# voicemodulator_schm.net
KiCad netlist of a schematic drawn in EAGLE
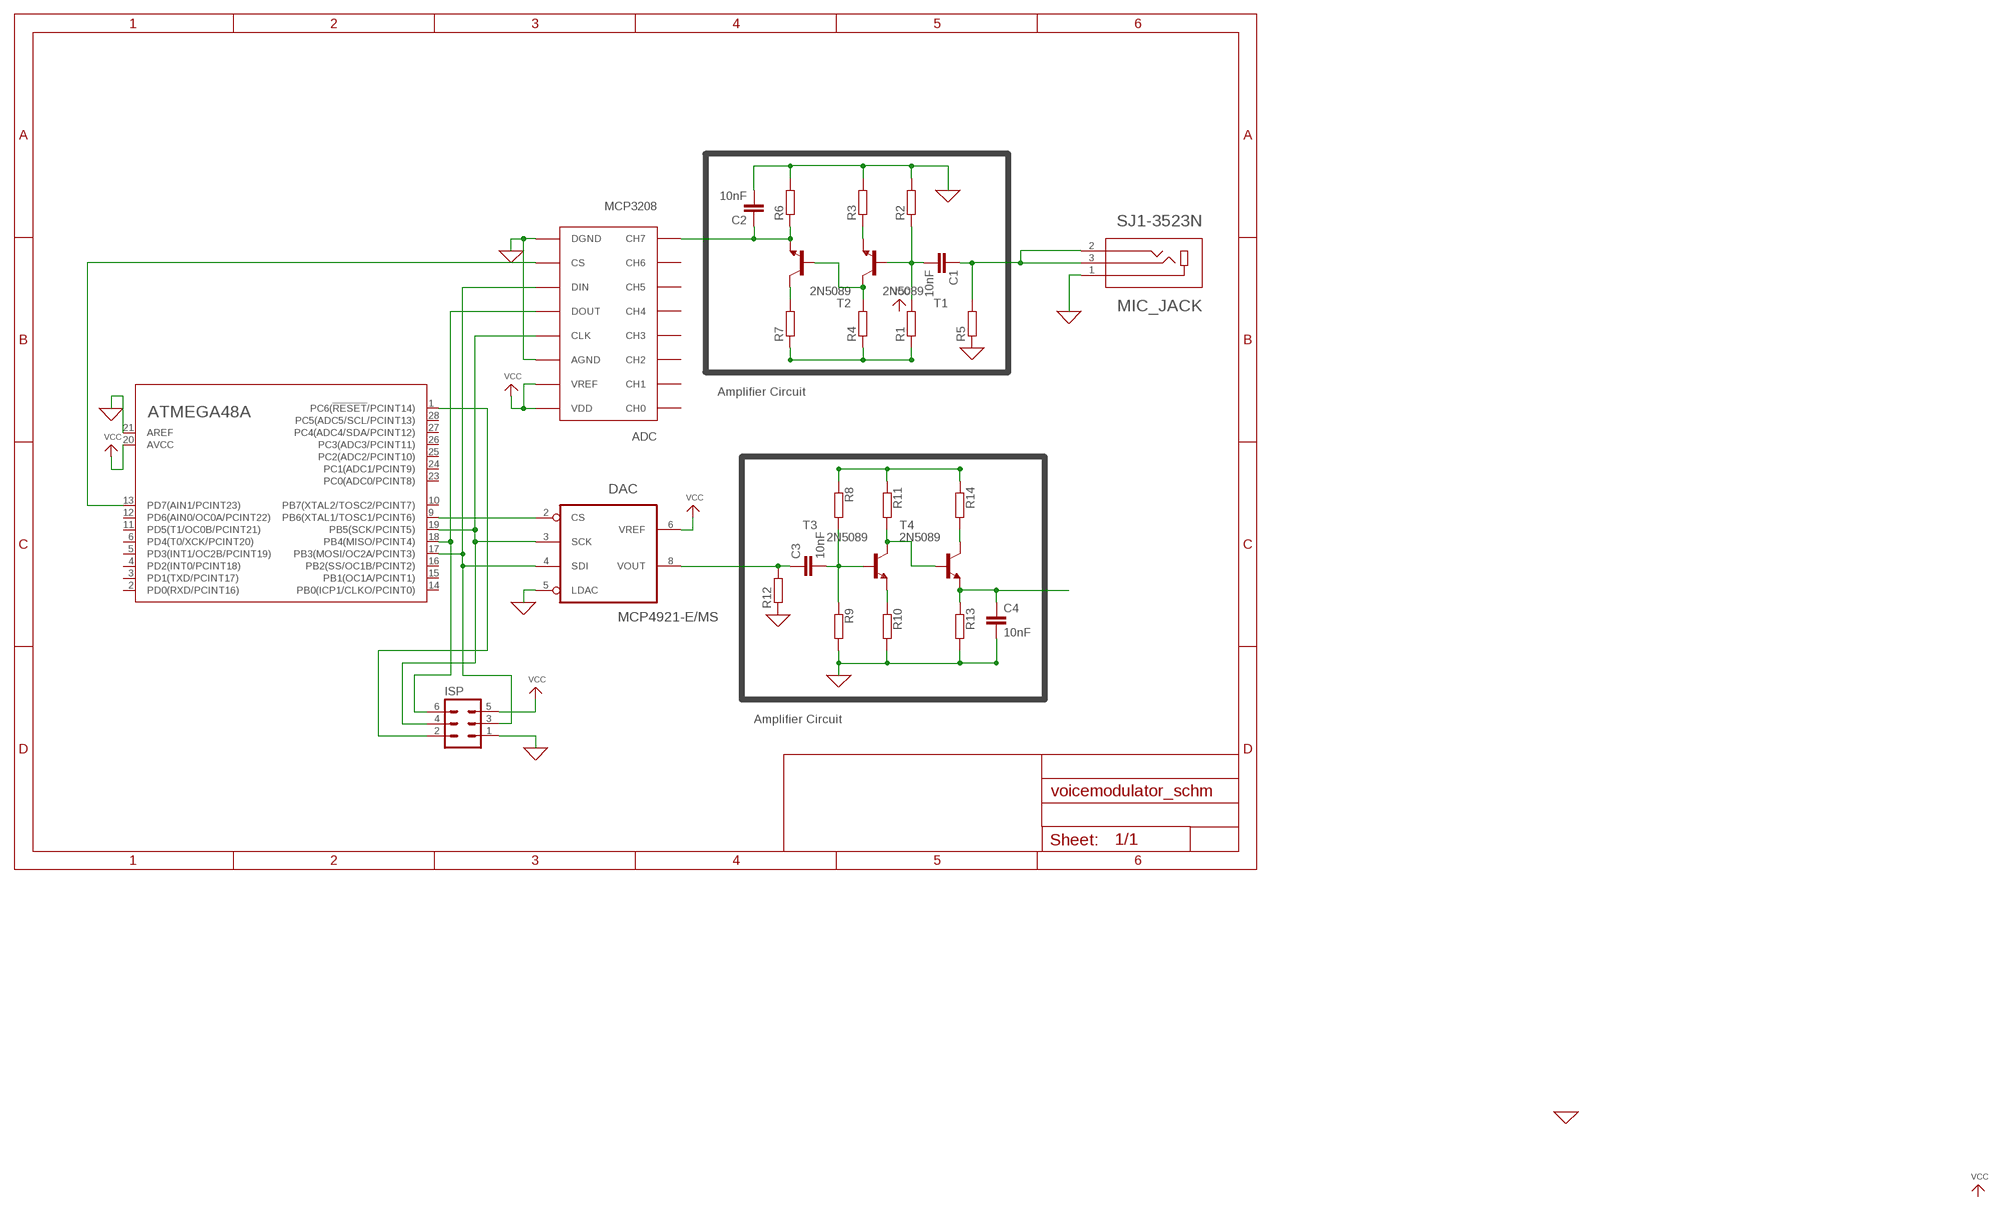
[diagram p0: schematic, sheet 1]

(export (version "E")
  (design (tool "Eeschema 10.0.6"))
  (components
    (comp (ref "ADC")
      (value "MCP3208")
      (footprint "eagle-import:DIL16")
      (libsource (lib "eagle-import") (part "MCP3208"))
    )
    (comp (ref "ATMEGA48A")
      (value "ATMEGA48/88/168/328-PU(DIP28)PU")
      (footprint "eagle-import:DIL28")
      (libsource (lib "eagle-import") (part "ATMEGA48/88/168/328-PU(DIP28)PU"))
    )
    (comp (ref "C1")
      (value "10nF")
      (footprint "eagle-import:0603")
      (libsource (lib "eagle-import") (part "10NF-0603-50V-10%"))
    )
    (comp (ref "C2")
      (value "10nF")
      (footprint "eagle-import:0603")
      (libsource (lib "eagle-import") (part "10NF-0603-50V-10%"))
    )
    (comp (ref "C3")
      (value "10nF")
      (footprint "eagle-import:0603")
      (libsource (lib "eagle-import") (part "10NF-0603-50V-10%"))
    )
    (comp (ref "C4")
      (value "10nF")
      (footprint "eagle-import:0603")
      (libsource (lib "eagle-import") (part "10NF-0603-50V-10%"))
    )
    (comp (ref "DAC")
      (value "MCP4921-E/MS")
      (footprint "eagle-import:MSOP-8")
      (libsource (lib "eagle-import") (part "MCP491-E/MS2"))
    )
    (comp (ref "ISP")
      (value "MA03-2")
      (footprint "eagle-import:MA03-2")
      (libsource (lib "eagle-import") (part "MA03-2"))
    )
    (comp (ref "MIC_JACK")
      (value "SJ1-3523N")
      (footprint "eagle-import:CUI_SJ1-3523N")
      (fields (field (name "MANUFACTURER") "CUI"))
      (libsource (lib "eagle-import") (part "SJ1-3523N"))
    )
    (comp (ref "R1")
      (value "SMR-WAV")
      (footprint "eagle-import:SMS-WAV")
      (libsource (lib "eagle-import") (part "SMR-WAV"))
    )
    (comp (ref "R2")
      (value "SMR-WAV")
      (footprint "eagle-import:SMS-WAV")
      (libsource (lib "eagle-import") (part "SMR-WAV"))
    )
    (comp (ref "R3")
      (value "SMR-WAV")
      (footprint "eagle-import:SMS-WAV")
      (libsource (lib "eagle-import") (part "SMR-WAV"))
    )
    (comp (ref "R4")
      (value "SMR-WAV")
      (footprint "eagle-import:SMS-WAV")
      (libsource (lib "eagle-import") (part "SMR-WAV"))
    )
    (comp (ref "R5")
      (value "SMR-WAV")
      (footprint "eagle-import:SMS-WAV")
      (libsource (lib "eagle-import") (part "SMR-WAV"))
    )
    (comp (ref "R6")
      (value "SMR-WAV")
      (footprint "eagle-import:SMS-WAV")
      (libsource (lib "eagle-import") (part "SMR-WAV"))
    )
    (comp (ref "R7")
      (value "SMR-WAV")
      (footprint "eagle-import:SMS-WAV")
      (libsource (lib "eagle-import") (part "SMR-WAV"))
    )
    (comp (ref "R8")
      (value "SMR-WAV")
      (footprint "eagle-import:SMS-WAV")
      (libsource (lib "eagle-import") (part "SMR-WAV"))
    )
    (comp (ref "R9")
      (value "SMR-WAV")
      (footprint "eagle-import:SMS-WAV")
      (libsource (lib "eagle-import") (part "SMR-WAV"))
    )
    (comp (ref "R10")
      (value "SMR-WAV")
      (footprint "eagle-import:SMS-WAV")
      (libsource (lib "eagle-import") (part "SMR-WAV"))
    )
    (comp (ref "R11")
      (value "SMR-WAV")
      (footprint "eagle-import:SMS-WAV")
      (libsource (lib "eagle-import") (part "SMR-WAV"))
    )
    (comp (ref "R12")
      (value "SMR-WAV")
      (footprint "eagle-import:SMS-WAV")
      (libsource (lib "eagle-import") (part "SMR-WAV"))
    )
    (comp (ref "R13")
      (value "SMR-WAV")
      (footprint "eagle-import:SMS-WAV")
      (libsource (lib "eagle-import") (part "SMR-WAV"))
    )
    (comp (ref "R14")
      (value "SMR-WAV")
      (footprint "eagle-import:SMS-WAV")
      (libsource (lib "eagle-import") (part "SMR-WAV"))
    )
    (comp (ref "T1")
      (value "2N5089")
      (footprint "eagle-import:TO92")
      (libsource (lib "eagle-import") (part "2N5089"))
    )
    (comp (ref "T2")
      (value "2N5089")
      (footprint "eagle-import:TO92")
      (libsource (lib "eagle-import") (part "2N5089"))
    )
    (comp (ref "T3")
      (value "2N5089")
      (footprint "eagle-import:TO92")
      (libsource (lib "eagle-import") (part "2N5089"))
    )
    (comp (ref "T4")
      (value "2N5089")
      (footprint "eagle-import:TO92")
      (libsource (lib "eagle-import") (part "2N5089"))
    )
  )
  (nets
    (net (code "1") (name "GND") (class "Default")
      (node (ref "ADC") (pin "AGND") (pinfunction "AGND_AGND") (pintype "power_in"))
      (node (ref "ADC") (pin "DGND") (pinfunction "DGND_DGND") (pintype "power_in"))
      (node (ref "ATMEGA48A") (pin "21") (pinfunction "AREF_21") (pintype "passive"))
      (node (ref "C2") (pin "2") (pinfunction "2_2") (pintype "passive"))
      (node (ref "C4") (pin "2") (pinfunction "2_2") (pintype "passive"))
      (node (ref "DAC") (pin "5") (pinfunction "LDAC_5") (pintype "input"))
      (node (ref "ISP") (pin "1") (pinfunction "1_1") (pintype "passive"))
      (node (ref "MIC_JACK") (pin "1") (pinfunction "1_1") (pintype "passive"))
      (node (ref "R10") (pin "1") (pinfunction "1_1") (pintype "passive"))
      (node (ref "R12") (pin "2") (pinfunction "2_2") (pintype "passive"))
      (node (ref "R13") (pin "1") (pinfunction "1_1") (pintype "passive"))
      (node (ref "R2") (pin "1") (pinfunction "1_1") (pintype "passive"))
      (node (ref "R3") (pin "1") (pinfunction "1_1") (pintype "passive"))
      (node (ref "R5") (pin "2") (pinfunction "2_2") (pintype "passive"))
      (node (ref "R6") (pin "1") (pinfunction "1_1") (pintype "passive"))
      (node (ref "R9") (pin "1") (pinfunction "1_1") (pintype "passive"))
    )
    (net (code "2") (name "Net-(ATMEGA48AA-PB3(MOSI{slash}OC2A{slash}PCINT3))") (class "Default")
      (node (ref "ADC") (pin "DIN") (pinfunction "DIN_DIN") (pintype "input"))
      (node (ref "ATMEGA48A") (pin "17") (pinfunction "PB3(MOSI/OC2A/PCINT3)_17") (pintype "bidirectional"))
      (node (ref "DAC") (pin "4") (pinfunction "SDI_4") (pintype "input"))
      (node (ref "ISP") (pin "3") (pinfunction "3_3") (pintype "passive"))
    )
    (net (code "3") (name "Net-(ATMEGA48AA-PB4(MISO{slash}PCINT4))") (class "Default")
      (node (ref "ADC") (pin "DOUT") (pinfunction "DOUT_DOUT") (pintype "output"))
      (node (ref "ATMEGA48A") (pin "18") (pinfunction "PB4(MISO/PCINT4)_18") (pintype "bidirectional"))
      (node (ref "ISP") (pin "6") (pinfunction "6_6") (pintype "passive"))
    )
    (net (code "4") (name "Net-(ATMEGA48AA-PB5(SCK{slash}PCINT5))") (class "Default")
      (node (ref "ADC") (pin "CLK") (pinfunction "CLK_CLK") (pintype "input"))
      (node (ref "ATMEGA48A") (pin "19") (pinfunction "PB5(SCK/PCINT5)_19") (pintype "bidirectional"))
      (node (ref "DAC") (pin "3") (pinfunction "SCK_3") (pintype "input"))
      (node (ref "ISP") (pin "4") (pinfunction "4_4") (pintype "passive"))
    )
    (net (code "5") (name "Net-(ATMEGA48AA-PB6(XTAL1{slash}TOSC1{slash}PCINT6))") (class "Default")
      (node (ref "ATMEGA48A") (pin "9") (pinfunction "PB6(XTAL1/TOSC1/PCINT6)_9") (pintype "bidirectional"))
      (node (ref "DAC") (pin "2") (pinfunction "CS_2") (pintype "input"))
    )
    (net (code "6") (name "Net-(ATMEGA48AA-PC6(~{RESET}{slash}PCINT14))") (class "Default")
      (node (ref "ATMEGA48A") (pin "1") (pinfunction "PC6(~{RESET}/PCINT14)_1") (pintype "bidirectional"))
      (node (ref "ISP") (pin "2") (pinfunction "2_2") (pintype "passive"))
    )
    (net (code "7") (name "Net-(ATMEGA48AA-PD7(AIN1{slash}PCINT23))") (class "Default")
      (node (ref "ADC") (pin "CS") (pinfunction "CS_CS") (pintype "input"))
      (node (ref "ATMEGA48A") (pin "13") (pinfunction "PD7(AIN1/PCINT23)_13") (pintype "bidirectional"))
    )
    (net (code "8") (name "Net-(C1-Pad1)") (class "Default")
      (node (ref "C1") (pin "1") (pinfunction "1_1") (pintype "passive"))
      (node (ref "MIC_JACK") (pin "2") (pinfunction "2_2") (pintype "passive"))
      (node (ref "MIC_JACK") (pin "3") (pinfunction "3_3") (pintype "passive"))
      (node (ref "R5") (pin "1") (pinfunction "1_1") (pintype "passive"))
    )
    (net (code "9") (name "Net-(DACA-VOUT)") (class "Default")
      (node (ref "C3") (pin "1") (pinfunction "1_1") (pintype "passive"))
      (node (ref "DAC") (pin "8") (pinfunction "VOUT_8") (pintype "output"))
      (node (ref "R12") (pin "1") (pinfunction "1_1") (pintype "passive"))
    )
    (net (code "10") (name "Net-(R1-Pad2)") (class "Default")
      (node (ref "R1") (pin "2") (pinfunction "2_2") (pintype "passive"))
      (node (ref "R4") (pin "2") (pinfunction "2_2") (pintype "passive"))
      (node (ref "R7") (pin "2") (pinfunction "2_2") (pintype "passive"))
    )
    (net (code "11") (name "Net-(R11-Pad2)") (class "Default")
      (node (ref "R11") (pin "2") (pinfunction "2_2") (pintype "passive"))
      (node (ref "R14") (pin "2") (pinfunction "2_2") (pintype "passive"))
      (node (ref "R8") (pin "2") (pinfunction "2_2") (pintype "passive"))
    )
    (net (code "12") (name "Net-(T1-B)") (class "Default")
      (node (ref "C1") (pin "2") (pinfunction "2_2") (pintype "passive"))
      (node (ref "R1") (pin "1") (pinfunction "1_1") (pintype "passive"))
      (node (ref "R2") (pin "2") (pinfunction "2_2") (pintype "passive"))
      (node (ref "T1") (pin "2") (pinfunction "B_2") (pintype "passive"))
    )
    (net (code "13") (name "Net-(T1-C)") (class "Default")
      (node (ref "R4") (pin "1") (pinfunction "1_1") (pintype "passive"))
      (node (ref "T1") (pin "1") (pinfunction "C_1") (pintype "passive"))
      (node (ref "T2") (pin "2") (pinfunction "B_2") (pintype "passive"))
    )
    (net (code "14") (name "Net-(T1-E)") (class "Default")
      (node (ref "R3") (pin "2") (pinfunction "2_2") (pintype "passive"))
      (node (ref "T1") (pin "3") (pinfunction "E_3") (pintype "passive"))
    )
    (net (code "15") (name "Net-(T2-C)") (class "Default")
      (node (ref "R7") (pin "1") (pinfunction "1_1") (pintype "passive"))
      (node (ref "T2") (pin "1") (pinfunction "C_1") (pintype "passive"))
    )
    (net (code "16") (name "Net-(T2-E)") (class "Default")
      (node (ref "ADC") (pin "CH7") (pinfunction "CH7_CH7") (pintype "input"))
      (node (ref "C2") (pin "1") (pinfunction "1_1") (pintype "passive"))
      (node (ref "R6") (pin "2") (pinfunction "2_2") (pintype "passive"))
      (node (ref "T2") (pin "3") (pinfunction "E_3") (pintype "passive"))
    )
    (net (code "17") (name "Net-(T3-B)") (class "Default")
      (node (ref "C3") (pin "2") (pinfunction "2_2") (pintype "passive"))
      (node (ref "R8") (pin "1") (pinfunction "1_1") (pintype "passive"))
      (node (ref "R9") (pin "2") (pinfunction "2_2") (pintype "passive"))
      (node (ref "T3") (pin "2") (pinfunction "B_2") (pintype "passive"))
    )
    (net (code "18") (name "Net-(T3-C)") (class "Default")
      (node (ref "R11") (pin "1") (pinfunction "1_1") (pintype "passive"))
      (node (ref "T3") (pin "1") (pinfunction "C_1") (pintype "passive"))
      (node (ref "T4") (pin "2") (pinfunction "B_2") (pintype "passive"))
    )
    (net (code "19") (name "Net-(T3-E)") (class "Default")
      (node (ref "R10") (pin "2") (pinfunction "2_2") (pintype "passive"))
      (node (ref "T3") (pin "3") (pinfunction "E_3") (pintype "passive"))
    )
    (net (code "20") (name "Net-(T4-C)") (class "Default")
      (node (ref "R14") (pin "1") (pinfunction "1_1") (pintype "passive"))
      (node (ref "T4") (pin "1") (pinfunction "C_1") (pintype "passive"))
    )
    (net (code "21") (name "Net-(T4-E)") (class "Default")
      (node (ref "C4") (pin "1") (pinfunction "1_1") (pintype "passive"))
      (node (ref "R13") (pin "2") (pinfunction "2_2") (pintype "passive"))
      (node (ref "T4") (pin "3") (pinfunction "E_3") (pintype "passive"))
    )
    (net (code "22") (name "VCC") (class "Default")
      (node (ref "ADC") (pin "VDD") (pinfunction "VDD_VDD") (pintype "power_in"))
      (node (ref "ADC") (pin "VREF") (pinfunction "VREF_VREF") (pintype "input"))
      (node (ref "ATMEGA48A") (pin "20") (pinfunction "AVCC_20") (pintype "power_in"))
      (node (ref "DAC") (pin "6") (pinfunction "VREF_6") (pintype "input"))
      (node (ref "ISP") (pin "5") (pinfunction "5_5") (pintype "passive"))
    )
    (net (code "23") (name "unconnected-(ADC-PadCH0)") (class "Default")
      (node (ref "ADC") (pin "CH0") (pinfunction "CH0_CH0") (pintype "input"))
    )
    (net (code "24") (name "unconnected-(ADC-PadCH1)") (class "Default")
      (node (ref "ADC") (pin "CH1") (pinfunction "CH1_CH1") (pintype "input"))
    )
    (net (code "25") (name "unconnected-(ADC-PadCH2)") (class "Default")
      (node (ref "ADC") (pin "CH2") (pinfunction "CH2_CH2") (pintype "input"))
    )
    (net (code "26") (name "unconnected-(ADC-PadCH3)") (class "Default")
      (node (ref "ADC") (pin "CH3") (pinfunction "CH3_CH3") (pintype "input"))
    )
    (net (code "27") (name "unconnected-(ADC-PadCH4)") (class "Default")
      (node (ref "ADC") (pin "CH4") (pinfunction "CH4_CH4") (pintype "input"))
    )
    (net (code "28") (name "unconnected-(ADC-PadCH5)") (class "Default")
      (node (ref "ADC") (pin "CH5") (pinfunction "CH5_CH5") (pintype "input"))
    )
    (net (code "29") (name "unconnected-(ADC-PadCH6)") (class "Default")
      (node (ref "ADC") (pin "CH6") (pinfunction "CH6_CH6") (pintype "input"))
    )
    (net (code "30") (name "unconnected-(ATMEGA48AA-PB0(ICP1{slash}CLKO{slash}PCINT0)-Pad14)") (class "Default")
      (node (ref "ATMEGA48A") (pin "14") (pinfunction "PB0(ICP1/CLKO/PCINT0)_14") (pintype "bidirectional"))
    )
    (net (code "31") (name "unconnected-(ATMEGA48AA-PB1(OC1A{slash}PCINT1)-Pad15)") (class "Default")
      (node (ref "ATMEGA48A") (pin "15") (pinfunction "PB1(OC1A/PCINT1)_15") (pintype "bidirectional"))
    )
    (net (code "32") (name "unconnected-(ATMEGA48AA-PB2(SS{slash}OC1B{slash}PCINT2)-Pad16)") (class "Default")
      (node (ref "ATMEGA48A") (pin "16") (pinfunction "PB2(SS/OC1B/PCINT2)_16") (pintype "bidirectional"))
    )
    (net (code "33") (name "unconnected-(ATMEGA48AA-PB7(XTAL2{slash}TOSC2{slash}PCINT7)-Pad10)") (class "Default")
      (node (ref "ATMEGA48A") (pin "10") (pinfunction "PB7(XTAL2/TOSC2/PCINT7)_10") (pintype "bidirectional"))
    )
    (net (code "34") (name "unconnected-(ATMEGA48AA-PC0(ADC0{slash}PCINT8)-Pad23)") (class "Default")
      (node (ref "ATMEGA48A") (pin "23") (pinfunction "PC0(ADC0/PCINT8)_23") (pintype "bidirectional"))
    )
    (net (code "35") (name "unconnected-(ATMEGA48AA-PC1(ADC1{slash}PCINT9)-Pad24)") (class "Default")
      (node (ref "ATMEGA48A") (pin "24") (pinfunction "PC1(ADC1/PCINT9)_24") (pintype "bidirectional"))
    )
    (net (code "36") (name "unconnected-(ATMEGA48AA-PC2(ADC2{slash}PCINT10)-Pad25)") (class "Default")
      (node (ref "ATMEGA48A") (pin "25") (pinfunction "PC2(ADC2/PCINT10)_25") (pintype "bidirectional"))
    )
    (net (code "37") (name "unconnected-(ATMEGA48AA-PC3(ADC3{slash}PCINT11)-Pad26)") (class "Default")
      (node (ref "ATMEGA48A") (pin "26") (pinfunction "PC3(ADC3/PCINT11)_26") (pintype "bidirectional"))
    )
    (net (code "38") (name "unconnected-(ATMEGA48AA-PC4(ADC4{slash}SDA{slash}PCINT12)-Pad27)") (class "Default")
      (node (ref "ATMEGA48A") (pin "27") (pinfunction "PC4(ADC4/SDA/PCINT12)_27") (pintype "bidirectional"))
    )
    (net (code "39") (name "unconnected-(ATMEGA48AA-PC5(ADC5{slash}SCL{slash}PCINT13)-Pad28)") (class "Default")
      (node (ref "ATMEGA48A") (pin "28") (pinfunction "PC5(ADC5/SCL/PCINT13)_28") (pintype "bidirectional"))
    )
    (net (code "40") (name "unconnected-(ATMEGA48AA-PD0(RXD{slash}PCINT16)-Pad2)") (class "Default")
      (node (ref "ATMEGA48A") (pin "2") (pinfunction "PD0(RXD/PCINT16)_2") (pintype "bidirectional"))
    )
    (net (code "41") (name "unconnected-(ATMEGA48AA-PD1(TXD{slash}PCINT17)-Pad3)") (class "Default")
      (node (ref "ATMEGA48A") (pin "3") (pinfunction "PD1(TXD/PCINT17)_3") (pintype "bidirectional"))
    )
    (net (code "42") (name "unconnected-(ATMEGA48AA-PD2(INT0{slash}PCINT18)-Pad4)") (class "Default")
      (node (ref "ATMEGA48A") (pin "4") (pinfunction "PD2(INT0/PCINT18)_4") (pintype "bidirectional"))
    )
    (net (code "43") (name "unconnected-(ATMEGA48AA-PD3(INT1{slash}OC2B{slash}PCINT19)-Pad5)") (class "Default")
      (node (ref "ATMEGA48A") (pin "5") (pinfunction "PD3(INT1/OC2B/PCINT19)_5") (pintype "bidirectional"))
    )
    (net (code "44") (name "unconnected-(ATMEGA48AA-PD4(T0{slash}XCK{slash}PCINT20)-Pad6)") (class "Default")
      (node (ref "ATMEGA48A") (pin "6") (pinfunction "PD4(T0/XCK/PCINT20)_6") (pintype "bidirectional"))
    )
    (net (code "45") (name "unconnected-(ATMEGA48AA-PD5(T1{slash}OC0B{slash}PCINT21)-Pad11)") (class "Default")
      (node (ref "ATMEGA48A") (pin "11") (pinfunction "PD5(T1/OC0B/PCINT21)_11") (pintype "bidirectional"))
    )
    (net (code "46") (name "unconnected-(ATMEGA48AA-PD6(AIN0{slash}OC0A{slash}PCINT22)-Pad12)") (class "Default")
      (node (ref "ATMEGA48A") (pin "12") (pinfunction "PD6(AIN0/OC0A/PCINT22)_12") (pintype "bidirectional"))
    )
  )
)
